# Rev5.net
KiCad netlist of a schematic drawn in Altium Designer
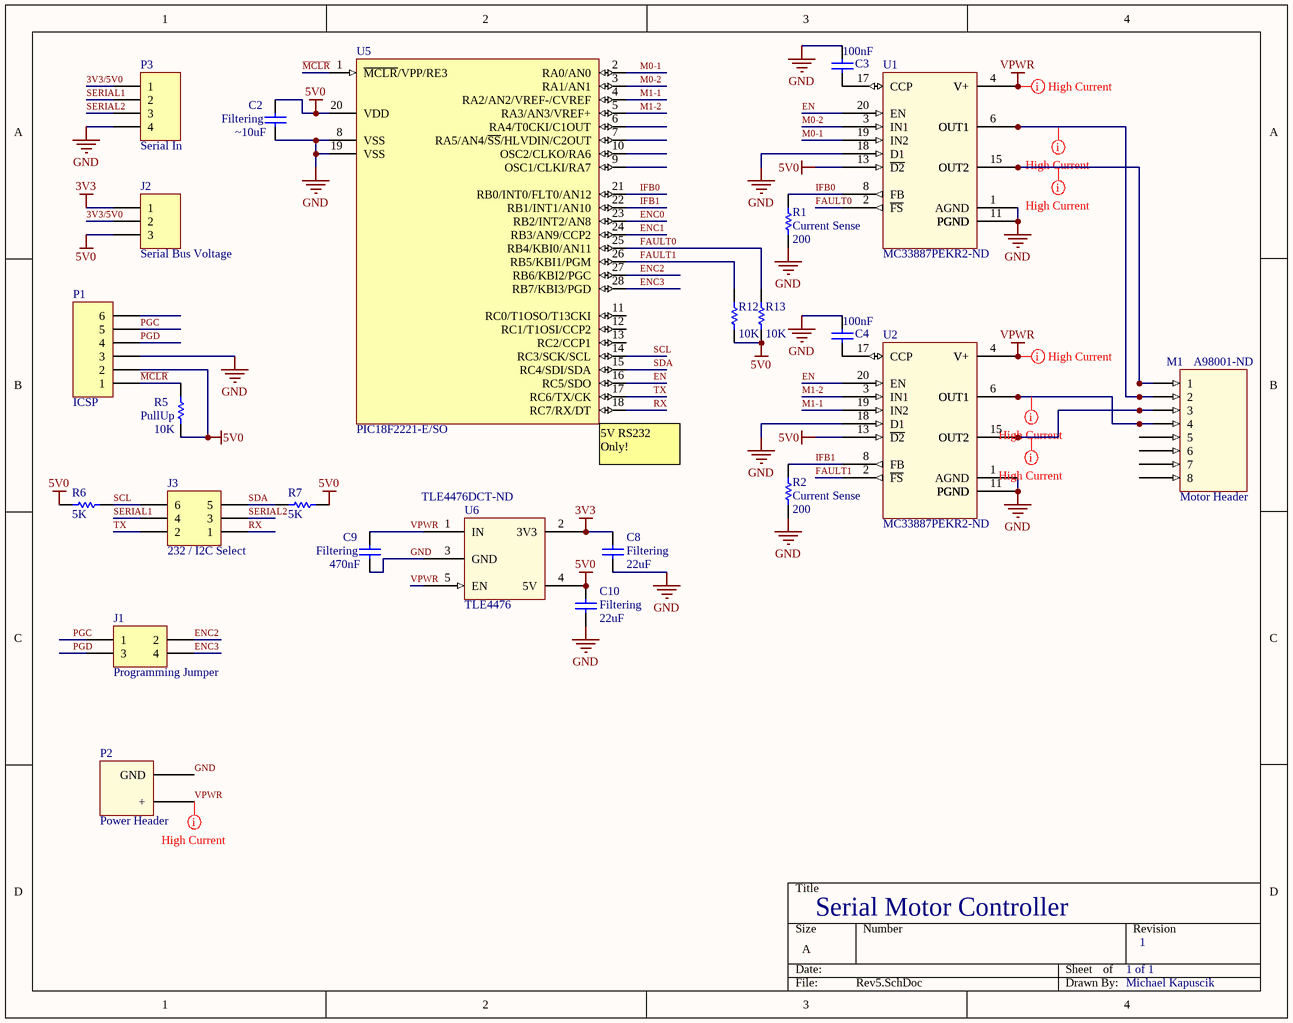
[diagram p0: Rev5.SchDoc]

(export (version "E")
  (design (tool "Eeschema 10.0.6"))
  (components
    (comp (ref "C2")
      (value "Filtering")
      (footprint "CAPR2.54-5.1x3.2")
      (description "Capacitor")
      (fields (field (name "ALTIUM_VALUE") "~10uF") (field (name "PUBLISHER") "Altium Limited"))
      (libsource (lib "Miscellaneous Devices") (part "Cap"))
    )
    (comp (ref "C3")
      (value "100nF")
      (footprint "CAPR2.54-5.1x3.2")
      (description "Capacitor")
      (fields (field (name "Comment") "Cap") (field (name "PUBLISHER") "Altium Limited"))
      (libsource (lib "Miscellaneous Devices") (part "Cap"))
    )
    (comp (ref "C4")
      (value "100nF")
      (footprint "CAPR2.54-5.1x3.2")
      (description "Capacitor")
      (fields (field (name "Comment") "Cap") (field (name "PUBLISHER") "Altium Limited"))
      (libsource (lib "Miscellaneous Devices") (part "Cap"))
    )
    (comp (ref "C8")
      (value "Filtering")
      (footprint "CAPR2.54-5.1x3.2")
      (description "Capacitor")
      (fields (field (name "ALTIUM_VALUE") "22uF") (field (name "PUBLISHER") "Altium Limited"))
      (libsource (lib "Miscellaneous Devices") (part "Cap"))
    )
    (comp (ref "C9")
      (value "Filtering")
      (footprint "CAPR2.54-5.1x3.2")
      (description "Capacitor")
      (fields (field (name "ALTIUM_VALUE") "470nF") (field (name "PUBLISHER") "Altium Limited"))
      (libsource (lib "Miscellaneous Devices") (part "Cap"))
    )
    (comp (ref "C10")
      (value "Filtering")
      (footprint "CAPR2.54-5.1x3.2")
      (description "Capacitor")
      (fields (field (name "ALTIUM_VALUE") "22uF") (field (name "PUBLISHER") "Altium Limited"))
      (libsource (lib "Miscellaneous Devices") (part "Cap"))
    )
    (comp (ref "J1")
      (value "Programming Jumper")
      (footprint "HDR2X2")
      (description "Header, 2-Pin, Dual row")
      (fields (field (name "PUBLISHER") "Altium Limited"))
      (libsource (lib "Miscellaneous Connectors") (part "Header 2X2"))
    )
    (comp (ref "J2")
      (value "Serial Bus Voltage")
      (footprint "HDR1X3")
      (description "Header, 3-Pin")
      (fields (field (name "PUBLISHER") "Altium Limited"))
      (libsource (lib "Miscellaneous Connectors") (part "Header 3"))
    )
    (comp (ref "J3")
      (value "232 / I2C Select")
      (footprint "HDR2X3")
      (description "Header, 3-Pin, Dual row")
      (fields (field (name "PUBLISHER") "Altium Limited"))
      (libsource (lib "Miscellaneous Connectors") (part "Header 3X2"))
    )
    (comp (ref "M1")
      (value "Motor Header")
      (footprint "Motor Header")
      (fields (field (name "SUPPLIER PART NUMBER 1") "A98001-ND"))
      (libsource (lib "Schlib1") (part "Motor Header"))
    )
    (comp (ref "P1")
      (value "ICSP")
      (footprint "HDR1X6")
      (description "Header, 6-Pin")
      (fields (field (name "PUBLISHER") "Altium Limited"))
      (libsource (lib "Miscellaneous Connectors") (part "Header 6"))
    )
    (comp (ref "P2")
      (value "Power Header")
      (footprint "Power Header")
      (libsource (lib "Schlib1") (part "Power Header"))
    )
    (comp (ref "P3")
      (value "Serial In")
      (footprint "HDR1X4")
      (description "Header, 4-Pin")
      (fields (field (name "PUBLISHER") "Altium Limited"))
      (libsource (lib "Miscellaneous Connectors") (part "Header 4"))
    )
    (comp (ref "R1")
      (value "Current Sense")
      (footprint "AXIAL-0.3")
      (description "1% Non Wirewound")
      (fields (field (name "ALTIUM_VALUE") "200") (field (name "PUBLISHER") "Altium Limited"))
      (libsource (lib "Miscellaneous Devices") (part "Res1"))
    )
    (comp (ref "R2")
      (value "Current Sense")
      (footprint "AXIAL-0.3")
      (description "Resistor")
      (fields (field (name "ALTIUM_VALUE") "200") (field (name "PUBLISHER") "Altium Limited"))
      (libsource (lib "Miscellaneous Devices") (part "Res1"))
    )
    (comp (ref "R5")
      (value "PullUp")
      (footprint "AXIAL-0.3")
      (description "Resistor")
      (fields (field (name "ALTIUM_VALUE") "10K") (field (name "PUBLISHER") "Altium Limited"))
      (libsource (lib "Miscellaneous Devices") (part "Res1"))
    )
    (comp (ref "R6")
      (value "5K")
      (footprint "AXIAL-0.3")
      (description "Resistor")
      (fields (field (name "Comment") "Res1") (field (name "PUBLISHER") "Altium Limited"))
      (libsource (lib "Miscellaneous Devices") (part "Res1"))
    )
    (comp (ref "R7")
      (value "5K")
      (footprint "AXIAL-0.3")
      (description "Resistor")
      (fields (field (name "Comment") "Res1") (field (name "PUBLISHER") "Altium Limited"))
      (libsource (lib "Miscellaneous Devices") (part "Res1"))
    )
    (comp (ref "R12")
      (value "10K")
      (footprint "AXIAL-0.3")
      (description "Resistor")
      (fields (field (name "Comment") "PullUp") (field (name "PUBLISHER") "Altium Limited"))
      (libsource (lib "Miscellaneous Devices") (part "Res1"))
    )
    (comp (ref "R13")
      (value "10K")
      (footprint "AXIAL-0.3")
      (description "Resistor")
      (fields (field (name "Comment") "PullUp") (field (name "PUBLISHER") "Altium Limited"))
      (libsource (lib "Miscellaneous Devices") (part "Res1"))
    )
    (comp (ref "U1")
      (value "MC33887")
      (footprint "HSOP20 Freescale")
      (description "H-Bridge")
      (fields (field (name "SUPPLIER PART NUMBER 1") "MC33887PEKR2-ND"))
      (libsource (lib "Schlib1") (part "MC33887"))
    )
    (comp (ref "U2")
      (value "MC33887")
      (footprint "HSOP20 Freescale")
      (description "H-Bridge")
      (fields (field (name "SUPPLIER PART NUMBER 1") "MC33887PEKR2-ND"))
      (libsource (lib "Schlib1") (part "MC33887"))
    )
    (comp (ref "U5")
      (value "PIC18F2221-E/SO")
      (footprint "SOIC-SO28_N")
      (fields (field (name "PUBLISHER") "Altium Limited"))
      (libsource (lib "Microchip Microcontroller 8-Bit PIC18") (part "PIC18F2221-E/SO"))
    )
    (comp (ref "U6")
      (value "TLE4476")
      (footprint "PG-TO252-5-1")
      (description "3V3 / 5V0 LDO regulator")
      (fields (field (name "SUPPLIER PART NUMBER 1") "TLE4476DCT-ND"))
      (libsource (lib "Schlib1") (part "TLE4476"))
    )
  )
  (nets
    (net (code "1") (name "/3V3{slash}5V0") (class "Default")
      (node (ref "J2") (pin "2") (pinfunction "2_2") (pintype "passive"))
      (node (ref "P3") (pin "1") (pinfunction "1_1") (pintype "passive"))
    )
    (net (code "2") (name "/EN") (class "Default")
      (node (ref "U1") (pin "20") (pinfunction "EN_20") (pintype "input"))
      (node (ref "U2") (pin "20") (pinfunction "EN_20") (pintype "input"))
      (node (ref "U5") (pin "16") (pinfunction "RC5/SDO_16") (pintype "bidirectional"))
    )
    (net (code "3") (name "/ENC0") (class "Default")
      (node (ref "U5") (pin "23") (pinfunction "RB2/INT2/AN8_23") (pintype "bidirectional"))
    )
    (net (code "4") (name "/ENC1") (class "Default")
      (node (ref "U5") (pin "24") (pinfunction "RB3/AN9/CCP2_24") (pintype "bidirectional"))
    )
    (net (code "5") (name "/ENC2") (class "Default")
      (node (ref "J1") (pin "2") (pinfunction "2_2") (pintype "passive"))
      (node (ref "U5") (pin "27") (pinfunction "RB6/KBI2/PGC_27") (pintype "bidirectional"))
    )
    (net (code "6") (name "/ENC3") (class "Default")
      (node (ref "J1") (pin "4") (pinfunction "4_4") (pintype "passive"))
      (node (ref "U5") (pin "28") (pinfunction "RB7/KBI3/PGD_28") (pintype "bidirectional"))
    )
    (net (code "7") (name "/FAULT0") (class "Default")
      (node (ref "R13") (pin "2") (pinfunction "2_2") (pintype "passive"))
      (node (ref "U1") (pin "2") (pinfunction "~{FS}_2") (pintype "output"))
      (node (ref "U5") (pin "25") (pinfunction "RB4/KBI0/AN11_25") (pintype "bidirectional"))
    )
    (net (code "8") (name "/FAULT1") (class "Default")
      (node (ref "R12") (pin "2") (pinfunction "2_2") (pintype "passive"))
      (node (ref "U2") (pin "2") (pinfunction "~{FS}_2") (pintype "output"))
      (node (ref "U5") (pin "26") (pinfunction "RB5/KBI1/PGM_26") (pintype "bidirectional"))
    )
    (net (code "9") (name "/IFB0") (class "Default")
      (node (ref "R1") (pin "2") (pinfunction "2_2") (pintype "passive"))
      (node (ref "U1") (pin "8") (pinfunction "FB_8") (pintype "output"))
      (node (ref "U5") (pin "21") (pinfunction "RB0/INT0/FLT0/AN12_21") (pintype "bidirectional"))
    )
    (net (code "10") (name "/IFB1") (class "Default")
      (node (ref "R2") (pin "2") (pinfunction "2_2") (pintype "passive"))
      (node (ref "U2") (pin "8") (pinfunction "FB_8") (pintype "output"))
      (node (ref "U5") (pin "22") (pinfunction "RB1/INT1/AN10_22") (pintype "bidirectional"))
    )
    (net (code "11") (name "/M0-1") (class "Default")
      (node (ref "U1") (pin "19") (pinfunction "IN2_19") (pintype "input"))
      (node (ref "U5") (pin "2") (pinfunction "RA0/AN0_2") (pintype "bidirectional"))
    )
    (net (code "12") (name "/M0-2") (class "Default")
      (node (ref "U1") (pin "3") (pinfunction "IN1_3") (pintype "input"))
      (node (ref "U5") (pin "3") (pinfunction "RA1/AN1_3") (pintype "bidirectional"))
    )
    (net (code "13") (name "/M1-1") (class "Default")
      (node (ref "U2") (pin "19") (pinfunction "IN2_19") (pintype "input"))
      (node (ref "U5") (pin "4") (pinfunction "RA2/AN2/VREF-/CVREF_4") (pintype "bidirectional"))
    )
    (net (code "14") (name "/M1-2") (class "Default")
      (node (ref "U2") (pin "3") (pinfunction "IN1_3") (pintype "input"))
      (node (ref "U5") (pin "5") (pinfunction "RA3/AN3/VREF+_5") (pintype "bidirectional"))
    )
    (net (code "15") (name "/PGC") (class "Default")
      (node (ref "J1") (pin "1") (pinfunction "1_1") (pintype "passive"))
      (node (ref "P1") (pin "5") (pinfunction "5_5") (pintype "passive"))
    )
    (net (code "16") (name "/PGD") (class "Default")
      (node (ref "J1") (pin "3") (pinfunction "3_3") (pintype "passive"))
      (node (ref "P1") (pin "4") (pinfunction "4_4") (pintype "passive"))
    )
    (net (code "17") (name "/RX") (class "Default")
      (node (ref "J3") (pin "1") (pinfunction "1_1") (pintype "passive"))
      (node (ref "U5") (pin "18") (pinfunction "RC7/RX/DT_18") (pintype "bidirectional"))
    )
    (net (code "18") (name "/SCL") (class "Default")
      (node (ref "J3") (pin "6") (pinfunction "6_6") (pintype "passive"))
      (node (ref "R6") (pin "1") (pinfunction "1_1") (pintype "passive"))
      (node (ref "U5") (pin "14") (pinfunction "RC3/SCK/SCL_14") (pintype "bidirectional"))
    )
    (net (code "19") (name "/SDA") (class "Default")
      (node (ref "J3") (pin "5") (pinfunction "5_5") (pintype "passive"))
      (node (ref "R7") (pin "1") (pinfunction "1_1") (pintype "passive"))
      (node (ref "U5") (pin "15") (pinfunction "RC4/SDI/SDA_15") (pintype "bidirectional"))
    )
    (net (code "20") (name "/SERIAL1") (class "Default")
      (node (ref "J3") (pin "4") (pinfunction "4_4") (pintype "passive"))
      (node (ref "P3") (pin "2") (pinfunction "2_2") (pintype "passive"))
    )
    (net (code "21") (name "/SERIAL2") (class "Default")
      (node (ref "J3") (pin "3") (pinfunction "3_3") (pintype "passive"))
      (node (ref "P3") (pin "3") (pinfunction "3_3") (pintype "passive"))
    )
    (net (code "22") (name "/TX") (class "Default")
      (node (ref "J3") (pin "2") (pinfunction "2_2") (pintype "passive"))
      (node (ref "U5") (pin "17") (pinfunction "RC6/TX/CK_17") (pintype "bidirectional"))
    )
    (net (code "23") (name "/~{MCLR}") (class "Default")
      (node (ref "P1") (pin "1") (pinfunction "1_1") (pintype "passive"))
      (node (ref "R5") (pin "2") (pinfunction "2_2") (pintype "passive"))
      (node (ref "U5") (pin "1") (pinfunction "~{MCLR}/VPP/RE3_1") (pintype "input"))
    )
    (net (code "24") (name "3V3") (class "Default")
      (node (ref "C8") (pin "2") (pinfunction "2_2") (pintype "passive"))
      (node (ref "J2") (pin "1") (pinfunction "1_1") (pintype "passive"))
      (node (ref "U6") (pin "2") (pinfunction "3V3_2") (pintype "power_in"))
    )
    (net (code "25") (name "5V0") (class "Default")
      (node (ref "C10") (pin "2") (pinfunction "2_2") (pintype "passive"))
      (node (ref "C2") (pin "1") (pinfunction "1_1") (pintype "passive"))
      (node (ref "J2") (pin "3") (pinfunction "3_3") (pintype "passive"))
      (node (ref "P1") (pin "2") (pinfunction "2_2") (pintype "passive"))
      (node (ref "R12") (pin "1") (pinfunction "1_1") (pintype "passive"))
      (node (ref "R13") (pin "1") (pinfunction "1_1") (pintype "passive"))
      (node (ref "R5") (pin "1") (pinfunction "1_1") (pintype "passive"))
      (node (ref "R6") (pin "2") (pinfunction "2_2") (pintype "passive"))
      (node (ref "R7") (pin "2") (pinfunction "2_2") (pintype "passive"))
      (node (ref "U1") (pin "13") (pinfunction "~{D2}_13") (pintype "input"))
      (node (ref "U2") (pin "13") (pinfunction "~{D2}_13") (pintype "input"))
      (node (ref "U5") (pin "20") (pinfunction "VDD_20") (pintype "power_in"))
      (node (ref "U6") (pin "4") (pinfunction "5V_4") (pintype "power_in"))
    )
    (net (code "26") (name "GND") (class "Default")
      (node (ref "C10") (pin "1") (pinfunction "1_1") (pintype "passive"))
      (node (ref "C2") (pin "2") (pinfunction "2_2") (pintype "passive"))
      (node (ref "C3") (pin "1") (pinfunction "1_1") (pintype "passive"))
      (node (ref "C4") (pin "1") (pinfunction "1_1") (pintype "passive"))
      (node (ref "C8") (pin "1") (pinfunction "1_1") (pintype "passive"))
      (node (ref "C9") (pin "1") (pinfunction "1_1") (pintype "passive"))
      (node (ref "P1") (pin "3") (pinfunction "3_3") (pintype "passive"))
      (node (ref "P2") (pin "2") (pinfunction "GND_2") (pintype "power_in"))
      (node (ref "P3") (pin "4") (pinfunction "4_4") (pintype "passive"))
      (node (ref "R1") (pin "1") (pinfunction "1_1") (pintype "passive"))
      (node (ref "R2") (pin "1") (pinfunction "1_1") (pintype "passive"))
      (node (ref "U1") (pin "1") (pinfunction "AGND_1") (pintype "power_in"))
      (node (ref "U1") (pin "10") (pinfunction "PGND_10") (pintype "power_in"))
      (node (ref "U1") (pin "11") (pinfunction "PGND_11") (pintype "power_in"))
      (node (ref "U1") (pin "12") (pinfunction "PGND_12") (pintype "power_in"))
      (node (ref "U1") (pin "18") (pinfunction "D1_18") (pintype "input"))
      (node (ref "U1") (pin "21") (pinfunction "PGND_21") (pintype "power_in"))
      (node (ref "U1") (pin "9") (pinfunction "PGND_9") (pintype "power_in"))
      (node (ref "U2") (pin "1") (pinfunction "AGND_1") (pintype "power_in"))
      (node (ref "U2") (pin "10") (pinfunction "PGND_10") (pintype "power_in"))
      (node (ref "U2") (pin "11") (pinfunction "PGND_11") (pintype "power_in"))
      (node (ref "U2") (pin "12") (pinfunction "PGND_12") (pintype "power_in"))
      (node (ref "U2") (pin "18") (pinfunction "D1_18") (pintype "input"))
      (node (ref "U2") (pin "21") (pinfunction "PGND_21") (pintype "power_in"))
      (node (ref "U2") (pin "9") (pinfunction "PGND_9") (pintype "power_in"))
      (node (ref "U5") (pin "19") (pinfunction "VSS_19") (pintype "power_in"))
      (node (ref "U5") (pin "8") (pinfunction "VSS_8") (pintype "power_in"))
      (node (ref "U6") (pin "3") (pinfunction "GND_3") (pintype "power_in"))
    )
    (net (code "27") (name "Net-(M1-Pad1)") (class "Default")
      (node (ref "M1") (pin "1") (pinfunction "1_1") (pintype "input"))
      (node (ref "U1") (pin "14") (pinfunction "OUT2_14") (pintype "power_in"))
      (node (ref "U1") (pin "15") (pinfunction "OUT2_15") (pintype "power_in"))
    )
    (net (code "28") (name "Net-(M1-Pad2)") (class "Default")
      (node (ref "M1") (pin "2") (pinfunction "2_2") (pintype "input"))
      (node (ref "U1") (pin "6") (pinfunction "OUT1_6") (pintype "power_in"))
      (node (ref "U1") (pin "7") (pinfunction "OUT1_7") (pintype "power_in"))
    )
    (net (code "29") (name "Net-(M1-Pad3)") (class "Default")
      (node (ref "M1") (pin "3") (pinfunction "3_3") (pintype "input"))
      (node (ref "U2") (pin "14") (pinfunction "OUT2_14") (pintype "power_in"))
      (node (ref "U2") (pin "15") (pinfunction "OUT2_15") (pintype "power_in"))
    )
    (net (code "30") (name "Net-(M1-Pad4)") (class "Default")
      (node (ref "M1") (pin "4") (pinfunction "4_4") (pintype "input"))
      (node (ref "U2") (pin "6") (pinfunction "OUT1_6") (pintype "power_in"))
      (node (ref "U2") (pin "7") (pinfunction "OUT1_7") (pintype "power_in"))
    )
    (net (code "31") (name "Net-(U1-CCP)") (class "Default")
      (node (ref "C3") (pin "2") (pinfunction "2_2") (pintype "passive"))
      (node (ref "U1") (pin "17") (pinfunction "CCP_17") (pintype "bidirectional"))
    )
    (net (code "32") (name "Net-(U2-CCP)") (class "Default")
      (node (ref "C4") (pin "2") (pinfunction "2_2") (pintype "passive"))
      (node (ref "U2") (pin "17") (pinfunction "CCP_17") (pintype "bidirectional"))
    )
    (net (code "33") (name "VPWR") (class "Default")
      (node (ref "C9") (pin "2") (pinfunction "2_2") (pintype "passive"))
      (node (ref "P2") (pin "1") (pinfunction "+_1") (pintype "power_in"))
      (node (ref "U1") (pin "16") (pinfunction "V+_16") (pintype "power_in"))
      (node (ref "U1") (pin "4") (pinfunction "V+_4") (pintype "power_in"))
      (node (ref "U1") (pin "5") (pinfunction "V+_5") (pintype "power_in"))
      (node (ref "U2") (pin "16") (pinfunction "V+_16") (pintype "power_in"))
      (node (ref "U2") (pin "4") (pinfunction "V+_4") (pintype "power_in"))
      (node (ref "U2") (pin "5") (pinfunction "V+_5") (pintype "power_in"))
      (node (ref "U6") (pin "1") (pinfunction "IN_1") (pintype "power_in"))
      (node (ref "U6") (pin "5") (pinfunction "EN_5") (pintype "input"))
    )
    (net (code "34") (name "unconnected-(M1-Pad5)") (class "Default")
      (node (ref "M1") (pin "5") (pinfunction "5_5") (pintype "input"))
    )
    (net (code "35") (name "unconnected-(M1-Pad6)") (class "Default")
      (node (ref "M1") (pin "6") (pinfunction "6_6") (pintype "input"))
    )
    (net (code "36") (name "unconnected-(M1-Pad7)") (class "Default")
      (node (ref "M1") (pin "7") (pinfunction "7_7") (pintype "input"))
    )
    (net (code "37") (name "unconnected-(M1-Pad8)") (class "Default")
      (node (ref "M1") (pin "8") (pinfunction "8_8") (pintype "input"))
    )
    (net (code "38") (name "unconnected-(P1-Pad6)") (class "Default")
      (node (ref "P1") (pin "6") (pinfunction "6_6") (pintype "passive"))
    )
    (net (code "39") (name "unconnected-(U5-OSC1{slash}CLKI{slash}RA7-Pad9)") (class "Default")
      (node (ref "U5") (pin "9") (pinfunction "OSC1/CLKI/RA7_9") (pintype "bidirectional"))
    )
    (net (code "40") (name "unconnected-(U5-OSC2{slash}CLKO{slash}RA6-Pad10)") (class "Default")
      (node (ref "U5") (pin "10") (pinfunction "OSC2/CLKO/RA6_10") (pintype "bidirectional"))
    )
    (net (code "41") (name "unconnected-(U5-RA4{slash}T0CKI{slash}C1OUT-Pad6)") (class "Default")
      (node (ref "U5") (pin "6") (pinfunction "RA4/T0CKI/C1OUT_6") (pintype "bidirectional"))
    )
    (net (code "42") (name "unconnected-(U5-RA5{slash}AN4{slash}~{SS}{slash}HLVDIN{slash}C2OUT-Pad7)") (class "Default")
      (node (ref "U5") (pin "7") (pinfunction "RA5/AN4/~{SS}/HLVDIN/C2OUT_7") (pintype "bidirectional"))
    )
    (net (code "43") (name "unconnected-(U5-RC0{slash}T1OSO{slash}T13CKI-Pad11)") (class "Default")
      (node (ref "U5") (pin "11") (pinfunction "RC0/T1OSO/T13CKI_11") (pintype "bidirectional"))
    )
    (net (code "44") (name "unconnected-(U5-RC1{slash}T1OSI{slash}CCP2-Pad12)") (class "Default")
      (node (ref "U5") (pin "12") (pinfunction "RC1/T1OSI/CCP2_12") (pintype "bidirectional"))
    )
    (net (code "45") (name "unconnected-(U5-RC2{slash}CCP1-Pad13)") (class "Default")
      (node (ref "U5") (pin "13") (pinfunction "RC2/CCP1_13") (pintype "bidirectional"))
    )
  )
)
